# dronesel5.net
KiCad netlist of a schematic drawn in EAGLE
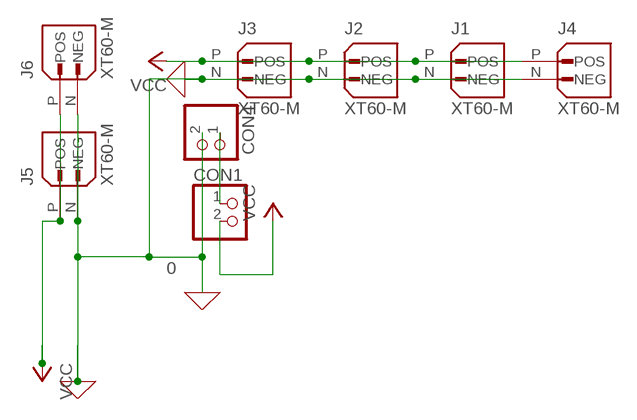
[diagram p0: schematic, sheet 1]

(export (version "E")
  (design (tool "Eeschema 10.0.6"))
  (components
    (comp (ref "CON1")
      (value "L2")
      (footprint "eagle-import:L_2")
      (libsource (lib "eagle-import") (part "L2"))
    )
    (comp (ref "CON4")
      (value "L2")
      (footprint "eagle-import:L_2")
      (libsource (lib "eagle-import") (part "L2"))
    )
    (comp (ref "J1")
      (value "XT60-M")
      (footprint "eagle-import:AMASS_XT60-M")
      (fields (field (name "MF") "AMASS"))
      (libsource (lib "eagle-import") (part "XT60-M"))
    )
    (comp (ref "J2")
      (value "XT60-M")
      (footprint "eagle-import:AMASS_XT60-M")
      (fields (field (name "MF") "AMASS"))
      (libsource (lib "eagle-import") (part "XT60-M"))
    )
    (comp (ref "J3")
      (value "XT60-M")
      (footprint "eagle-import:AMASS_XT60-M")
      (fields (field (name "MF") "AMASS"))
      (libsource (lib "eagle-import") (part "XT60-M"))
    )
    (comp (ref "J4")
      (value "XT60-M")
      (footprint "eagle-import:AMASS_XT60-M")
      (fields (field (name "MF") "AMASS"))
      (libsource (lib "eagle-import") (part "XT60-M"))
    )
    (comp (ref "J5")
      (value "XT60-M")
      (footprint "eagle-import:AMASS_XT60-M")
      (fields (field (name "MF") "AMASS"))
      (libsource (lib "eagle-import") (part "XT60-M"))
    )
    (comp (ref "J6")
      (value "XT60-M")
      (footprint "eagle-import:AMASS_XT60-M")
      (fields (field (name "MF") "AMASS"))
      (libsource (lib "eagle-import") (part "XT60-M"))
    )
  )
  (nets
    (net (code "1") (name "GND") (class "Default")
      (node (ref "CON4") (pin "2") (pinfunction "2_2") (pintype "passive"))
      (node (ref "J1") (pin "N") (pinfunction "NEG_N") (pintype "passive"))
      (node (ref "J2") (pin "N") (pinfunction "NEG_N") (pintype "passive"))
      (node (ref "J3") (pin "N") (pinfunction "NEG_N") (pintype "passive"))
      (node (ref "J4") (pin "N") (pinfunction "NEG_N") (pintype "passive"))
      (node (ref "J5") (pin "N") (pinfunction "NEG_N") (pintype "passive"))
      (node (ref "J6") (pin "N") (pinfunction "NEG_N") (pintype "passive"))
    )
    (net (code "2") (name "Net-(CON1-GND)") (class "Default")
      (node (ref "CON1") (pin "1") (pinfunction "GND_1") (pintype "passive"))
      (node (ref "CON4") (pin "1") (pinfunction "GND_1") (pintype "passive"))
    )
    (net (code "3") (name "VCC") (class "Default")
      (node (ref "CON1") (pin "2") (pinfunction "2_2") (pintype "passive"))
      (node (ref "J1") (pin "P") (pinfunction "POS_P") (pintype "passive"))
      (node (ref "J2") (pin "P") (pinfunction "POS_P") (pintype "passive"))
      (node (ref "J3") (pin "P") (pinfunction "POS_P") (pintype "passive"))
      (node (ref "J4") (pin "P") (pinfunction "POS_P") (pintype "passive"))
      (node (ref "J5") (pin "P") (pinfunction "POS_P") (pintype "passive"))
      (node (ref "J6") (pin "P") (pinfunction "POS_P") (pintype "passive"))
    )
  )
)
